# SD-Socket.net
KiCad netlist of a schematic drawn in Altium Designer
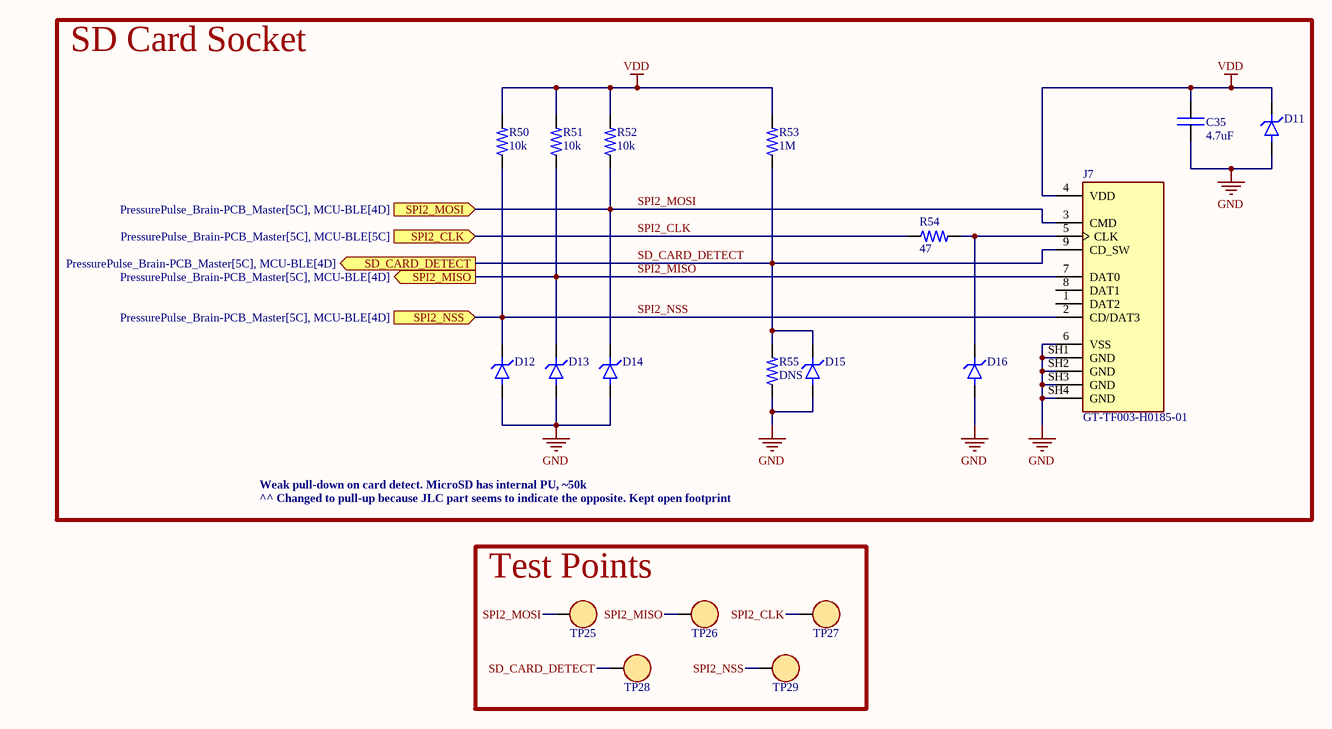
[diagram p0: SD-Socket.SchDoc]

(export (version "E")
  (design (tool "Eeschema 10.0.6"))
  (components
    (comp (ref "C35")
      (value "4.7uF")
      (footprint "PressurePulse:0402C")
      (description "Capacitor")
      (fields (field (name "Comment") "CAP"))
      (libsource (lib "PressurePulse") (part "CAP"))
    )
    (comp (ref "D11")
      (value "RCLAMP0521P.TCT")
      (footprint "PressurePulse:BDFN2C051V40")
      (description "25V Clamp 4A (8/20µs) Ipp Tvs Diode Surface Mount SLP1006P2")
      (fields (field (name "MFR") "BORN"))
      (libsource (lib "PressurePulse") (part "TVS DIODE"))
    )
    (comp (ref "D12")
      (value "RCLAMP0521P.TCT")
      (footprint "PressurePulse:BDFN2C051V40")
      (description "25V Clamp 4A (8/20µs) Ipp Tvs Diode Surface Mount SLP1006P2")
      (fields (field (name "MFR") "BORN"))
      (libsource (lib "PressurePulse") (part "TVS DIODE"))
    )
    (comp (ref "D13")
      (value "RCLAMP0521P.TCT")
      (footprint "PressurePulse:BDFN2C051V40")
      (description "25V Clamp 4A (8/20µs) Ipp Tvs Diode Surface Mount SLP1006P2")
      (fields (field (name "MFR") "BORN"))
      (libsource (lib "PressurePulse") (part "TVS DIODE"))
    )
    (comp (ref "D14")
      (value "RCLAMP0521P.TCT")
      (footprint "PressurePulse:BDFN2C051V40")
      (description "25V Clamp 4A (8/20µs) Ipp Tvs Diode Surface Mount SLP1006P2")
      (fields (field (name "MFR") "BORN"))
      (libsource (lib "PressurePulse") (part "TVS DIODE"))
    )
    (comp (ref "D15")
      (value "RCLAMP0521P.TCT")
      (footprint "PressurePulse:BDFN2C051V40")
      (description "25V Clamp 4A (8/20µs) Ipp Tvs Diode Surface Mount SLP1006P2")
      (fields (field (name "MFR") "BORN"))
      (libsource (lib "PressurePulse") (part "TVS DIODE"))
    )
    (comp (ref "D16")
      (value "RCLAMP0521P.TCT")
      (footprint "PressurePulse:BDFN2C051V40")
      (description "25V Clamp 4A (8/20µs) Ipp Tvs Diode Surface Mount SLP1006P2")
      (fields (field (name "MFR") "BORN"))
      (libsource (lib "PressurePulse") (part "TVS DIODE"))
    )
    (comp (ref "J7")
      (value "GT-TF003-H0185-01")
      (footprint "PressurePulse:GTTF003H018501")
      (fields (field (name "MFR") "G-Switch"))
      (libsource (lib "PressurePulse") (part "SD-CONN-SMD_JLC"))
    )
    (comp (ref "R50")
      (value "10k")
      (footprint "PressurePulse:0402R")
      (description "Resistor")
      (fields (field (name "Comment") "RES"))
      (libsource (lib "PressurePulse") (part "RES"))
    )
    (comp (ref "R51")
      (value "10k")
      (footprint "PressurePulse:0402R")
      (description "Resistor")
      (fields (field (name "Comment") "RES"))
      (libsource (lib "PressurePulse") (part "RES"))
    )
    (comp (ref "R52")
      (value "10k")
      (footprint "PressurePulse:0402R")
      (description "Resistor")
      (fields (field (name "Comment") "RES"))
      (libsource (lib "PressurePulse") (part "RES"))
    )
    (comp (ref "R53")
      (value "1M")
      (footprint "PressurePulse:0402R")
      (description "Resistor")
      (fields (field (name "Comment") "RES"))
      (libsource (lib "PressurePulse") (part "RES"))
    )
    (comp (ref "R54")
      (value "47")
      (footprint "PressurePulse:0402R")
      (description "Resistor")
      (fields (field (name "Comment") "RES"))
      (libsource (lib "PressurePulse") (part "RES"))
    )
    (comp (ref "R55")
      (value "DNS")
      (footprint "PressurePulse:0402R")
      (description "Resistor")
      (fields (field (name "Comment") "RES"))
      (libsource (lib "PressurePulse") (part "RES"))
    )
    (comp (ref "TP25")
      (value "RH-5019")
      (footprint "PressurePulse:TP - RH-5019")
      (fields (field (name "MFR") "ronghe"))
      (libsource (lib "PressurePulse") (part "TEST POINT"))
    )
    (comp (ref "TP26")
      (value "RH-5019")
      (footprint "PressurePulse:TP - RH-5019")
      (fields (field (name "MFR") "ronghe"))
      (libsource (lib "PressurePulse") (part "TEST POINT"))
    )
    (comp (ref "TP27")
      (value "RH-5019")
      (footprint "PressurePulse:TP - RH-5019")
      (fields (field (name "MFR") "ronghe"))
      (libsource (lib "PressurePulse") (part "TEST POINT"))
    )
    (comp (ref "TP28")
      (value "RH-5019")
      (footprint "PressurePulse:TP - RH-5019")
      (fields (field (name "MFR") "ronghe"))
      (libsource (lib "PressurePulse") (part "TEST POINT"))
    )
    (comp (ref "TP29")
      (value "RH-5019")
      (footprint "PressurePulse:TP - RH-5019")
      (fields (field (name "MFR") "ronghe"))
      (libsource (lib "PressurePulse") (part "TEST POINT"))
    )
  )
  (nets
    (net (code "1") (name "/SD_CARD_DETECT") (class "Default")
      (node (ref "D15") (pin "K") (pinfunction "K_K") (pintype "passive"))
      (node (ref "J7") (pin "9") (pinfunction "CD_SW_9") (pintype "passive"))
      (node (ref "R53") (pin "1") (pinfunction "1_1") (pintype "passive"))
      (node (ref "R55") (pin "2") (pinfunction "2_2") (pintype "passive"))
      (node (ref "TP28") (pin "1") (pinfunction "1_1") (pintype "passive"))
    )
    (net (code "2") (name "/SPI2_CLK") (class "Default")
      (node (ref "R54") (pin "1") (pinfunction "1_1") (pintype "passive"))
      (node (ref "TP27") (pin "1") (pinfunction "1_1") (pintype "passive"))
    )
    (net (code "3") (name "/SPI2_MISO") (class "Default")
      (node (ref "D13") (pin "K") (pinfunction "K_K") (pintype "passive"))
      (node (ref "J7") (pin "7") (pinfunction "DAT0_7") (pintype "passive"))
      (node (ref "R51") (pin "1") (pinfunction "1_1") (pintype "passive"))
      (node (ref "TP26") (pin "1") (pinfunction "1_1") (pintype "passive"))
    )
    (net (code "4") (name "/SPI2_MOSI") (class "Default")
      (node (ref "D14") (pin "K") (pinfunction "K_K") (pintype "passive"))
      (node (ref "J7") (pin "3") (pinfunction "CMD_3") (pintype "passive"))
      (node (ref "R52") (pin "1") (pinfunction "1_1") (pintype "passive"))
      (node (ref "TP25") (pin "1") (pinfunction "1_1") (pintype "passive"))
    )
    (net (code "5") (name "/SPI2_NSS") (class "Default")
      (node (ref "D12") (pin "K") (pinfunction "K_K") (pintype "passive"))
      (node (ref "J7") (pin "2") (pinfunction "CD/DAT3_2") (pintype "passive"))
      (node (ref "R50") (pin "1") (pinfunction "1_1") (pintype "passive"))
      (node (ref "TP29") (pin "1") (pinfunction "1_1") (pintype "passive"))
    )
    (net (code "6") (name "GND") (class "Default")
      (node (ref "C35") (pin "1") (pinfunction "1_1") (pintype "passive"))
      (node (ref "D11") (pin "A") (pinfunction "A_A") (pintype "passive"))
      (node (ref "D12") (pin "A") (pinfunction "A_A") (pintype "passive"))
      (node (ref "D13") (pin "A") (pinfunction "A_A") (pintype "passive"))
      (node (ref "D14") (pin "A") (pinfunction "A_A") (pintype "passive"))
      (node (ref "D15") (pin "A") (pinfunction "A_A") (pintype "passive"))
      (node (ref "D16") (pin "A") (pinfunction "A_A") (pintype "passive"))
      (node (ref "J7") (pin "6") (pinfunction "VSS_6") (pintype "passive"))
      (node (ref "J7") (pin "SH1") (pinfunction "GND_SH1") (pintype "passive"))
      (node (ref "J7") (pin "SH2") (pinfunction "GND_SH2") (pintype "passive"))
      (node (ref "J7") (pin "SH3") (pinfunction "GND_SH3") (pintype "passive"))
      (node (ref "J7") (pin "SH4") (pinfunction "GND_SH4") (pintype "passive"))
      (node (ref "R55") (pin "1") (pinfunction "1_1") (pintype "passive"))
    )
    (net (code "7") (name "Net-(J7-CLK)") (class "Default")
      (node (ref "D16") (pin "K") (pinfunction "K_K") (pintype "passive"))
      (node (ref "J7") (pin "5") (pinfunction "CLK_5") (pintype "passive"))
      (node (ref "R54") (pin "2") (pinfunction "2_2") (pintype "passive"))
    )
    (net (code "8") (name "VDD") (class "Default")
      (node (ref "C35") (pin "2") (pinfunction "2_2") (pintype "passive"))
      (node (ref "D11") (pin "K") (pinfunction "K_K") (pintype "passive"))
      (node (ref "J7") (pin "4") (pinfunction "VDD_4") (pintype "passive"))
      (node (ref "R50") (pin "2") (pinfunction "2_2") (pintype "passive"))
      (node (ref "R51") (pin "2") (pinfunction "2_2") (pintype "passive"))
      (node (ref "R52") (pin "2") (pinfunction "2_2") (pintype "passive"))
      (node (ref "R53") (pin "2") (pinfunction "2_2") (pintype "passive"))
    )
    (net (code "9") (name "unconnected-(J7-DAT1-Pad8)") (class "Default")
      (node (ref "J7") (pin "8") (pinfunction "DAT1_8") (pintype "passive"))
    )
    (net (code "10") (name "unconnected-(J7-DAT2-Pad1)") (class "Default")
      (node (ref "J7") (pin "1") (pinfunction "DAT2_1") (pintype "passive"))
    )
  )
)
